# AST1001.net
KiCad netlist of a schematic drawn in EAGLE
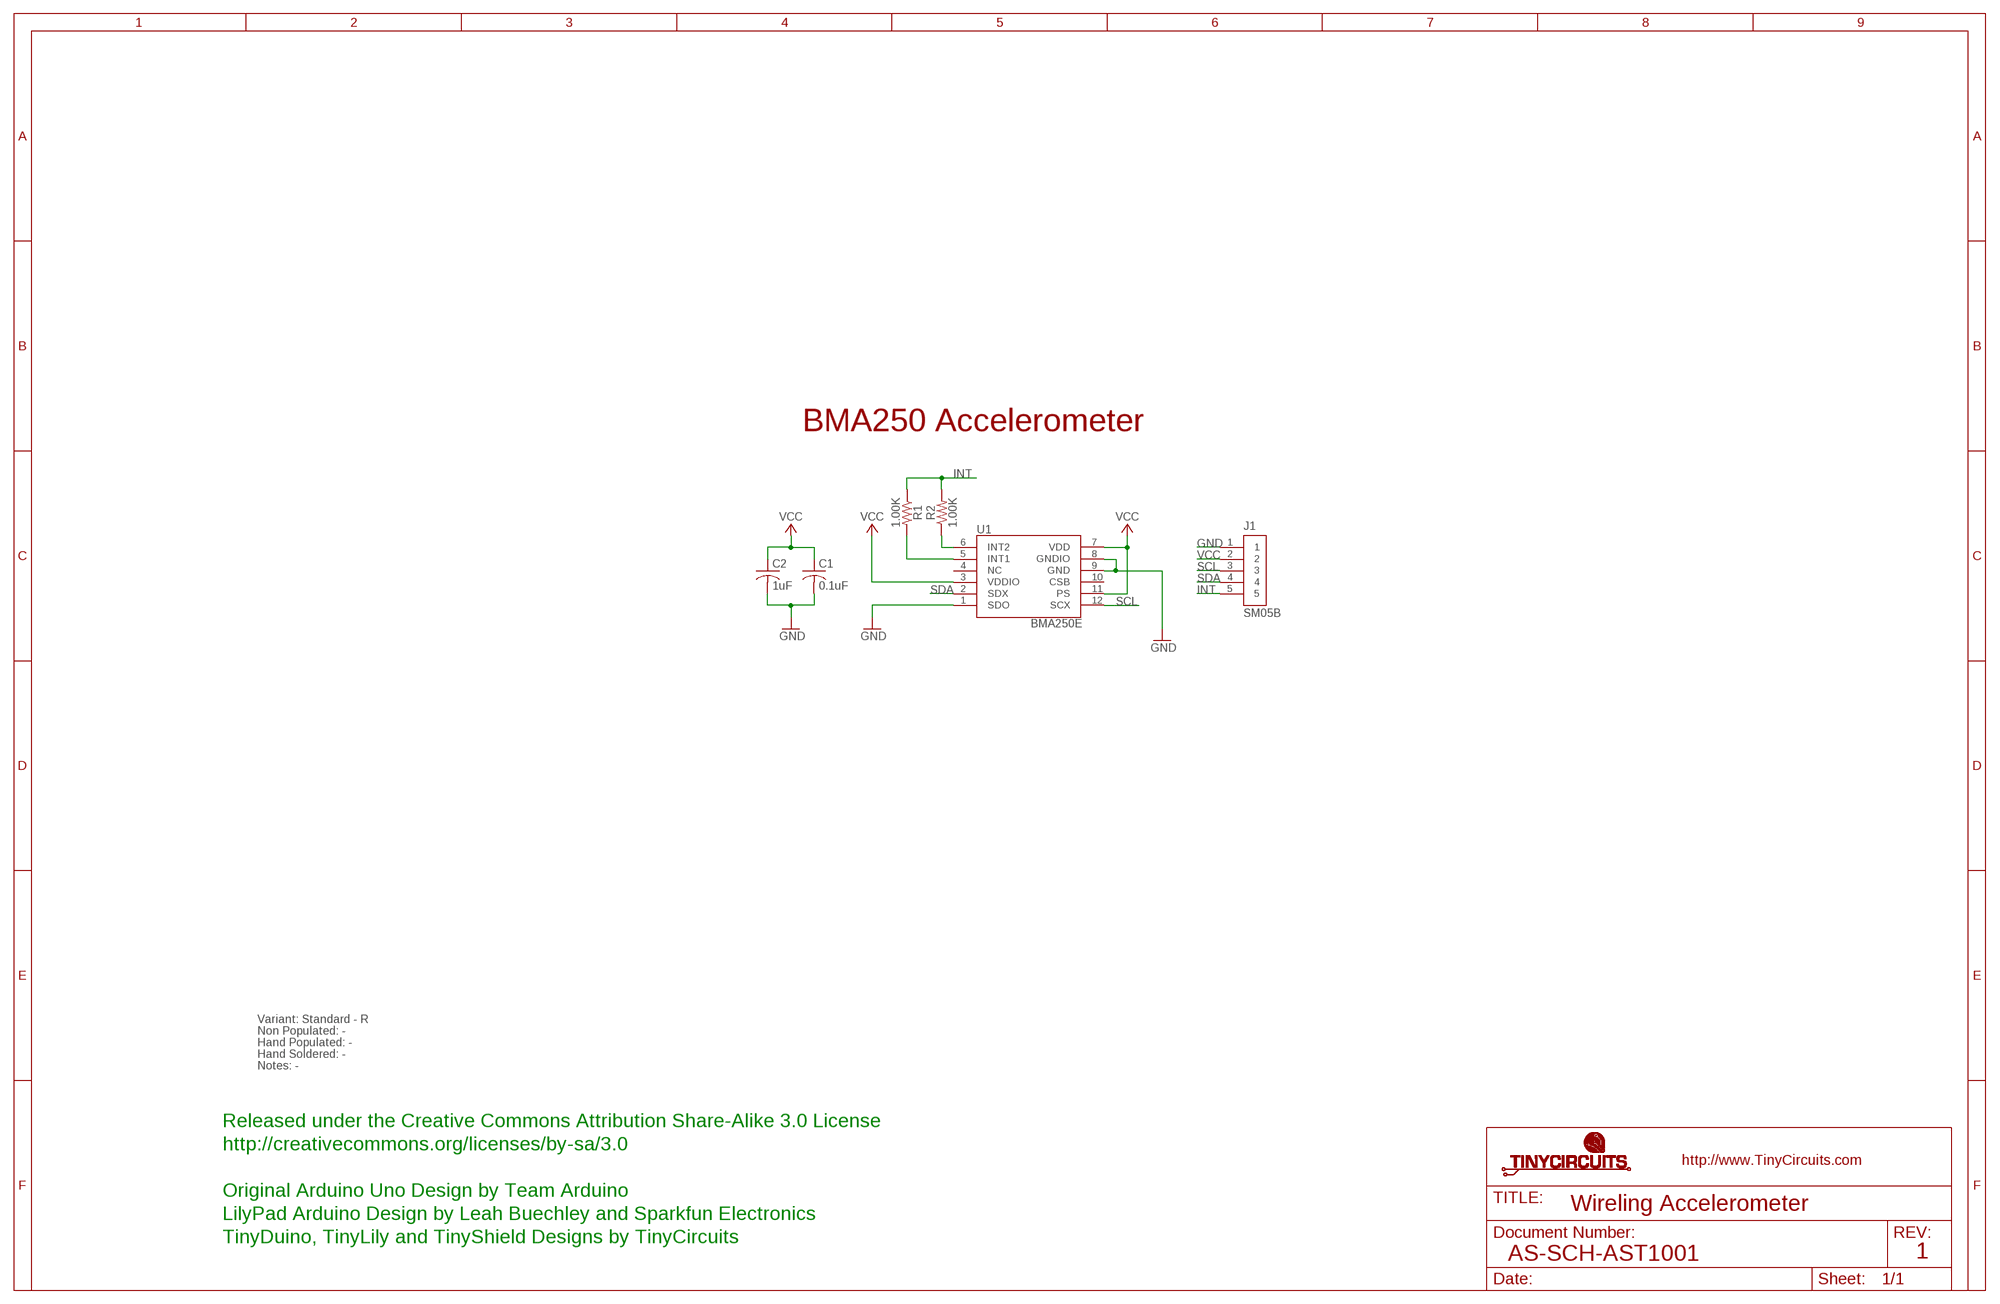
[diagram p0: schematic, sheet 1]

(export (version "E")
  (design (tool "Eeschema 10.0.6"))
  (components
    (comp (ref "C1")
      (value "0.1uF")
      (footprint "eagle-import:C0402")
      (fields (field (name "PARTNO") "AS-ITM-00008"))
      (libsource (lib "eagle-import") (part "AS-ITM-00008"))
    )
    (comp (ref "C2")
      (value "1uF")
      (footprint "eagle-import:C0603")
      (fields (field (name "PARTNO") "AS-ITM-00410") (field (name "PARTNO_1") "AS-ITM-00410"))
      (libsource (lib "eagle-import") (part "AS-ITM-00410"))
    )
    (comp (ref "J1")
      (value "SM05B")
      (footprint "eagle-import:JST_SH_5X1_EDGE")
      (fields (field (name "PARTNO") "AS-ITM-00340"))
      (libsource (lib "eagle-import") (part "AS-ITM-00340EDGE"))
    )
    (comp (ref "R1")
      (value "1.00K")
      (footprint "eagle-import:0402")
      (fields (field (name "PARTNO") "AS-ITM-00003") (field (name "PARTNO_1") "AS-ITM-00003"))
      (libsource (lib "eagle-import") (part "AS-ITM-00003"))
    )
    (comp (ref "R2")
      (value "1.00K")
      (footprint "eagle-import:0402")
      (fields (field (name "PARTNO") "AS-ITM-00003") (field (name "PARTNO_1") "AS-ITM-00003"))
      (libsource (lib "eagle-import") (part "AS-ITM-00003"))
    )
    (comp (ref "U1")
      (value "BMA250E")
      (footprint "eagle-import:3-AXIS_ACCELEROMETER")
      (fields (field (name "PARTNO") "AS-ITM-00070"))
      (libsource (lib "eagle-import") (part "AS-ITM-00070"))
    )
  )
  (nets
    (net (code "1") (name "/INT") (class "Default")
      (node (ref "J1") (pin "5") (pinfunction "5_5") (pintype "bidirectional"))
      (node (ref "R1") (pin "1") (pinfunction "1_1") (pintype "passive"))
      (node (ref "R2") (pin "2") (pinfunction "2_2") (pintype "passive"))
    )
    (net (code "2") (name "/SCL") (class "Default")
      (node (ref "J1") (pin "3") (pinfunction "3_3") (pintype "bidirectional"))
      (node (ref "U1") (pin "12") (pinfunction "SCX_12") (pintype "bidirectional"))
    )
    (net (code "3") (name "/SDA") (class "Default")
      (node (ref "J1") (pin "4") (pinfunction "4_4") (pintype "bidirectional"))
      (node (ref "U1") (pin "2") (pinfunction "SDX_2") (pintype "bidirectional"))
    )
    (net (code "4") (name "GND") (class "Default")
      (node (ref "C1") (pin "2") (pinfunction "2_2") (pintype "passive"))
      (node (ref "C2") (pin "2") (pinfunction "2_2") (pintype "passive"))
      (node (ref "J1") (pin "1") (pinfunction "1_1") (pintype "bidirectional"))
      (node (ref "U1") (pin "1") (pinfunction "SDO_1") (pintype "bidirectional"))
      (node (ref "U1") (pin "8") (pinfunction "GNDIO_8") (pintype "bidirectional"))
      (node (ref "U1") (pin "9") (pinfunction "GND_9") (pintype "bidirectional"))
    )
    (net (code "5") (name "Net-(U1-INT1)") (class "Default")
      (node (ref "R1") (pin "2") (pinfunction "2_2") (pintype "passive"))
      (node (ref "U1") (pin "5") (pinfunction "INT1_5") (pintype "bidirectional"))
    )
    (net (code "6") (name "Net-(U1-INT2)") (class "Default")
      (node (ref "R2") (pin "1") (pinfunction "1_1") (pintype "passive"))
      (node (ref "U1") (pin "6") (pinfunction "INT2_6") (pintype "bidirectional"))
    )
    (net (code "7") (name "VCC") (class "Default")
      (node (ref "C1") (pin "1") (pinfunction "1_1") (pintype "passive"))
      (node (ref "C2") (pin "1") (pinfunction "1_1") (pintype "passive"))
      (node (ref "J1") (pin "2") (pinfunction "2_2") (pintype "bidirectional"))
      (node (ref "U1") (pin "11") (pinfunction "PS_11") (pintype "bidirectional"))
      (node (ref "U1") (pin "3") (pinfunction "VDDIO_3") (pintype "bidirectional"))
      (node (ref "U1") (pin "7") (pinfunction "VDD_7") (pintype "bidirectional"))
    )
    (net (code "8") (name "unconnected-(U1-CSB-Pad10)") (class "Default")
      (node (ref "U1") (pin "10") (pinfunction "CSB_10") (pintype "bidirectional"))
    )
    (net (code "9") (name "unconnected-(U1-NC-Pad4)") (class "Default")
      (node (ref "U1") (pin "4") (pinfunction "NC_4") (pintype "bidirectional"))
    )
  )
)
